# Int_Hub.net
KiCad netlist of a schematic drawn in Altium Designer
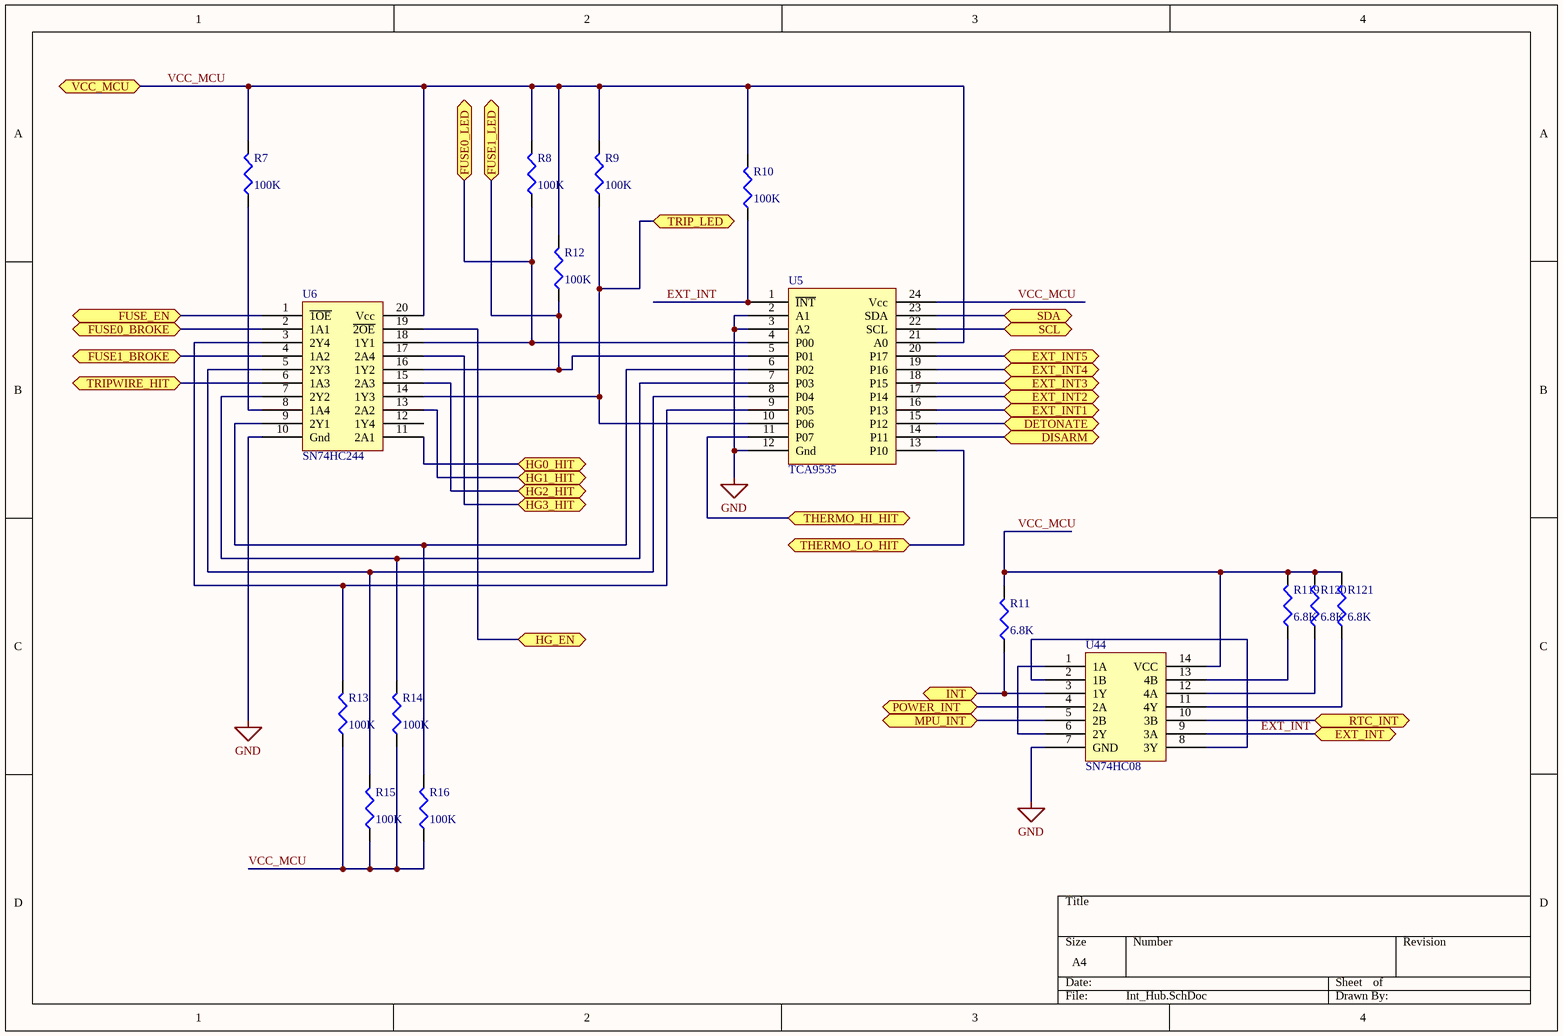
[diagram p0: Int_Hub.SchDoc]

(export (version "E")
  (design (tool "Eeschema 10.0.6"))
  (components
    (comp (ref "R7")
      (value "100K")
      (footprint "clock:0603")
      (description "Resistor")
      (fields (field (name "Comment") "Res3") (field (name "PUBLISHER") "Altium Limited"))
      (libsource (lib "Miscellaneous Devices") (part "Res3"))
    )
    (comp (ref "R8")
      (value "100K")
      (footprint "clock:0603")
      (description "Resistor")
      (fields (field (name "Comment") "Res3") (field (name "PUBLISHER") "Altium Limited"))
      (libsource (lib "Miscellaneous Devices") (part "Res3"))
    )
    (comp (ref "R9")
      (value "100K")
      (footprint "clock:0603")
      (description "Resistor")
      (fields (field (name "Comment") "Res3") (field (name "PUBLISHER") "Altium Limited"))
      (libsource (lib "Miscellaneous Devices") (part "Res3"))
    )
    (comp (ref "R10")
      (value "100K")
      (footprint "clock:0603")
      (description "Resistor")
      (fields (field (name "Comment") "Res3") (field (name "PUBLISHER") "Altium Limited"))
      (libsource (lib "Miscellaneous Devices") (part "Res3"))
    )
    (comp (ref "R11")
      (value "6.8K")
      (footprint "clock:0603")
      (description "Resistor")
      (fields (field (name "Comment") "Res3") (field (name "PUBLISHER") "Altium Limited"))
      (libsource (lib "Miscellaneous Devices") (part "Res3"))
    )
    (comp (ref "R12")
      (value "100K")
      (footprint "clock:0603")
      (description "Resistor")
      (fields (field (name "Comment") "Res3") (field (name "PUBLISHER") "Altium Limited"))
      (libsource (lib "Miscellaneous Devices") (part "Res3"))
    )
    (comp (ref "R13")
      (value "100K")
      (footprint "clock:0603")
      (description "Resistor")
      (fields (field (name "Comment") "Res3") (field (name "PUBLISHER") "Altium Limited"))
      (libsource (lib "Miscellaneous Devices") (part "Res3"))
    )
    (comp (ref "R14")
      (value "100K")
      (footprint "clock:0603")
      (description "Resistor")
      (fields (field (name "Comment") "Res3") (field (name "PUBLISHER") "Altium Limited"))
      (libsource (lib "Miscellaneous Devices") (part "Res3"))
    )
    (comp (ref "R15")
      (value "100K")
      (footprint "clock:0603")
      (description "Resistor")
      (fields (field (name "Comment") "Res3") (field (name "PUBLISHER") "Altium Limited"))
      (libsource (lib "Miscellaneous Devices") (part "Res3"))
    )
    (comp (ref "R16")
      (value "100K")
      (footprint "clock:0603")
      (description "Resistor")
      (fields (field (name "Comment") "Res3") (field (name "PUBLISHER") "Altium Limited"))
      (libsource (lib "Miscellaneous Devices") (part "Res3"))
    )
    (comp (ref "R119")
      (value "6.8K")
      (footprint "clock:0603")
      (description "Resistor")
      (fields (field (name "Comment") "Res3") (field (name "PUBLISHER") "Altium Limited"))
      (libsource (lib "Miscellaneous Devices") (part "Res3"))
    )
    (comp (ref "R120")
      (value "6.8K")
      (footprint "clock:0603")
      (description "Resistor")
      (fields (field (name "Comment") "Res3") (field (name "PUBLISHER") "Altium Limited"))
      (libsource (lib "Miscellaneous Devices") (part "Res3"))
    )
    (comp (ref "R121")
      (value "6.8K")
      (footprint "clock:0603")
      (description "Resistor")
      (fields (field (name "Comment") "Res3") (field (name "PUBLISHER") "Altium Limited"))
      (libsource (lib "Miscellaneous Devices") (part "Res3"))
    )
    (comp (ref "U5") (value "TCA9535") (footprint "clock:TSSOP24") (libsource (lib "clock") (part "TCA9535")))
    (comp (ref "U6")
      (value "SN74HC244")
      (footprint "clock:TSSOP20")
      (libsource (lib "clock") (part "SN74HC244"))
    )
    (comp (ref "U44")
      (value "SN74HC08")
      (footprint "clock:TSSOP14")
      (libsource (lib "clock") (part "SN74HC08"))
    )
  )
  (nets
    (net (code "1") (name "/DETONATE") (class "Default")
      (node (ref "U5") (pin "15") (pinfunction "P12_15") (pintype "passive"))
    )
    (net (code "2") (name "/DISARM") (class "Default")
      (node (ref "U5") (pin "14") (pinfunction "P11_14") (pintype "passive"))
    )
    (net (code "3") (name "/EXT_INT") (class "Default")
      (node (ref "R10") (pin "1") (pinfunction "1_1") (pintype "passive"))
      (node (ref "U44") (pin "9") (pinfunction "3A_9") (pintype "passive"))
      (node (ref "U5") (pin "1") (pinfunction "~{INT}_1") (pintype "passive"))
    )
    (net (code "4") (name "/EXT_INT1") (class "Default")
      (node (ref "U5") (pin "16") (pinfunction "P13_16") (pintype "passive"))
    )
    (net (code "5") (name "/EXT_INT2") (class "Default")
      (node (ref "U5") (pin "17") (pinfunction "P14_17") (pintype "passive"))
    )
    (net (code "6") (name "/EXT_INT3") (class "Default")
      (node (ref "U5") (pin "18") (pinfunction "P15_18") (pintype "passive"))
    )
    (net (code "7") (name "/EXT_INT4") (class "Default")
      (node (ref "U5") (pin "19") (pinfunction "P16_19") (pintype "passive"))
    )
    (net (code "8") (name "/EXT_INT5") (class "Default")
      (node (ref "U5") (pin "20") (pinfunction "P17_20") (pintype "passive"))
    )
    (net (code "9") (name "/FUSE0_BROKE") (class "Default")
      (node (ref "U6") (pin "2") (pinfunction "1A1_2") (pintype "passive"))
    )
    (net (code "10") (name "/FUSE0_LED") (class "Default")
      (node (ref "R8") (pin "1") (pinfunction "1_1") (pintype "passive"))
      (node (ref "U5") (pin "4") (pinfunction "P00_4") (pintype "passive"))
      (node (ref "U6") (pin "18") (pinfunction "1Y1_18") (pintype "passive"))
    )
    (net (code "11") (name "/FUSE1_BROKE") (class "Default")
      (node (ref "U6") (pin "4") (pinfunction "1A2_4") (pintype "passive"))
    )
    (net (code "12") (name "/FUSE1_LED") (class "Default")
      (node (ref "R12") (pin "1") (pinfunction "1_1") (pintype "passive"))
      (node (ref "U5") (pin "5") (pinfunction "P01_5") (pintype "passive"))
      (node (ref "U6") (pin "16") (pinfunction "1Y2_16") (pintype "passive"))
    )
    (net (code "13") (name "/FUSE_EN") (class "Default")
      (node (ref "U6") (pin "1") (pinfunction "~{1OE}_1") (pintype "passive"))
    )
    (net (code "14") (name "/HG0_HIT") (class "Default")
      (node (ref "U6") (pin "11") (pinfunction "2A1_11") (pintype "passive"))
    )
    (net (code "15") (name "/HG1_HIT") (class "Default")
      (node (ref "U6") (pin "13") (pinfunction "2A2_13") (pintype "passive"))
    )
    (net (code "16") (name "/HG2_HIT") (class "Default")
      (node (ref "U6") (pin "15") (pinfunction "2A3_15") (pintype "passive"))
    )
    (net (code "17") (name "/HG3_HIT") (class "Default")
      (node (ref "U6") (pin "17") (pinfunction "2A4_17") (pintype "passive"))
    )
    (net (code "18") (name "/HG_EN") (class "Default")
      (node (ref "U6") (pin "19") (pinfunction "~{2OE}_19") (pintype "passive"))
    )
    (net (code "19") (name "/INT") (class "Default")
      (node (ref "R11") (pin "1") (pinfunction "1_1") (pintype "passive"))
      (node (ref "U44") (pin "3") (pinfunction "1Y_3") (pintype "passive"))
    )
    (net (code "20") (name "/MPU_INT") (class "Default")
      (node (ref "U44") (pin "5") (pinfunction "2B_5") (pintype "passive"))
    )
    (net (code "21") (name "/POWER_INT") (class "Default")
      (node (ref "U44") (pin "4") (pinfunction "2A_4") (pintype "passive"))
    )
    (net (code "22") (name "/RTC_INT") (class "Default")
      (node (ref "U44") (pin "10") (pinfunction "3B_10") (pintype "passive"))
    )
    (net (code "23") (name "/SCL") (class "Default")
      (node (ref "U5") (pin "22") (pinfunction "SCL_22") (pintype "passive"))
    )
    (net (code "24") (name "/SDA") (class "Default")
      (node (ref "U5") (pin "23") (pinfunction "SDA_23") (pintype "passive"))
    )
    (net (code "25") (name "/THERMO_HI_HIT") (class "Default")
      (node (ref "U5") (pin "11") (pinfunction "P07_11") (pintype "passive"))
    )
    (net (code "26") (name "/THERMO_LO_HIT") (class "Default")
      (node (ref "U5") (pin "13") (pinfunction "P10_13") (pintype "passive"))
    )
    (net (code "27") (name "/TRIPWIRE_HIT") (class "Default")
      (node (ref "U6") (pin "6") (pinfunction "1A3_6") (pintype "passive"))
    )
    (net (code "28") (name "/TRIP_LED") (class "Default")
      (node (ref "R9") (pin "1") (pinfunction "1_1") (pintype "passive"))
      (node (ref "U5") (pin "10") (pinfunction "P06_10") (pintype "passive"))
      (node (ref "U6") (pin "14") (pinfunction "1Y3_14") (pintype "passive"))
    )
    (net (code "29") (name "/VCC_MCU") (class "Default")
      (node (ref "R10") (pin "2") (pinfunction "2_2") (pintype "passive"))
      (node (ref "R11") (pin "2") (pinfunction "2_2") (pintype "passive"))
      (node (ref "R119") (pin "2") (pinfunction "2_2") (pintype "passive"))
      (node (ref "R12") (pin "2") (pinfunction "2_2") (pintype "passive"))
      (node (ref "R120") (pin "2") (pinfunction "2_2") (pintype "passive"))
      (node (ref "R121") (pin "2") (pinfunction "2_2") (pintype "passive"))
      (node (ref "R13") (pin "1") (pinfunction "1_1") (pintype "passive"))
      (node (ref "R14") (pin "1") (pinfunction "1_1") (pintype "passive"))
      (node (ref "R15") (pin "1") (pinfunction "1_1") (pintype "passive"))
      (node (ref "R16") (pin "1") (pinfunction "1_1") (pintype "passive"))
      (node (ref "R7") (pin "2") (pinfunction "2_2") (pintype "passive"))
      (node (ref "R8") (pin "2") (pinfunction "2_2") (pintype "passive"))
      (node (ref "R9") (pin "2") (pinfunction "2_2") (pintype "passive"))
      (node (ref "U44") (pin "14") (pinfunction "VCC_14") (pintype "passive"))
      (node (ref "U5") (pin "21") (pinfunction "A0_21") (pintype "passive"))
      (node (ref "U5") (pin "24") (pinfunction "Vcc_24") (pintype "passive"))
      (node (ref "U6") (pin "20") (pinfunction "Vcc_20") (pintype "passive"))
    )
    (net (code "30") (name "GND") (class "Default")
      (node (ref "U44") (pin "7") (pinfunction "GND_7") (pintype "passive"))
      (node (ref "U5") (pin "12") (pinfunction "Gnd_12") (pintype "passive"))
      (node (ref "U5") (pin "2") (pinfunction "A1_2") (pintype "passive"))
      (node (ref "U5") (pin "3") (pinfunction "A2_3") (pintype "passive"))
      (node (ref "U6") (pin "10") (pinfunction "Gnd_10") (pintype "passive"))
    )
    (net (code "31") (name "Net-(U5-P02)") (class "Default")
      (node (ref "R16") (pin "2") (pinfunction "2_2") (pintype "passive"))
      (node (ref "U5") (pin "6") (pinfunction "P02_6") (pintype "passive"))
      (node (ref "U6") (pin "9") (pinfunction "2Y1_9") (pintype "passive"))
    )
    (net (code "32") (name "Net-(U5-P03)") (class "Default")
      (node (ref "R14") (pin "2") (pinfunction "2_2") (pintype "passive"))
      (node (ref "U5") (pin "7") (pinfunction "P03_7") (pintype "passive"))
      (node (ref "U6") (pin "7") (pinfunction "2Y2_7") (pintype "passive"))
    )
    (net (code "33") (name "Net-(U5-P04)") (class "Default")
      (node (ref "R15") (pin "2") (pinfunction "2_2") (pintype "passive"))
      (node (ref "U5") (pin "8") (pinfunction "P04_8") (pintype "passive"))
      (node (ref "U6") (pin "5") (pinfunction "2Y3_5") (pintype "passive"))
    )
    (net (code "34") (name "Net-(U5-P05)") (class "Default")
      (node (ref "R13") (pin "2") (pinfunction "2_2") (pintype "passive"))
      (node (ref "U5") (pin "9") (pinfunction "P05_9") (pintype "passive"))
      (node (ref "U6") (pin "3") (pinfunction "2Y4_3") (pintype "passive"))
    )
    (net (code "35") (name "Net-(U6-1A4)") (class "Default")
      (node (ref "R7") (pin "1") (pinfunction "1_1") (pintype "passive"))
      (node (ref "U6") (pin "8") (pinfunction "1A4_8") (pintype "passive"))
    )
    (net (code "36") (name "Net-(U44-1A)") (class "Default")
      (node (ref "U44") (pin "1") (pinfunction "1A_1") (pintype "passive"))
      (node (ref "U44") (pin "6") (pinfunction "2Y_6") (pintype "passive"))
    )
    (net (code "37") (name "Net-(U44-1B)") (class "Default")
      (node (ref "U44") (pin "2") (pinfunction "1B_2") (pintype "passive"))
      (node (ref "U44") (pin "8") (pinfunction "3Y_8") (pintype "passive"))
    )
    (net (code "38") (name "Net-(U44-4A)") (class "Default")
      (node (ref "R120") (pin "1") (pinfunction "1_1") (pintype "passive"))
      (node (ref "U44") (pin "12") (pinfunction "4A_12") (pintype "passive"))
    )
    (net (code "39") (name "Net-(U44-4B)") (class "Default")
      (node (ref "R119") (pin "1") (pinfunction "1_1") (pintype "passive"))
      (node (ref "U44") (pin "13") (pinfunction "4B_13") (pintype "passive"))
    )
    (net (code "40") (name "Net-(U44-4Y)") (class "Default")
      (node (ref "R121") (pin "1") (pinfunction "1_1") (pintype "passive"))
      (node (ref "U44") (pin "11") (pinfunction "4Y_11") (pintype "passive"))
    )
    (net (code "41") (name "unconnected-(U6-1Y4-Pad12)") (class "Default")
      (node (ref "U6") (pin "12") (pinfunction "1Y4_12") (pintype "passive"))
    )
  )
)
